# Greippi.net
KiCad netlist of a schematic drawn in EAGLE
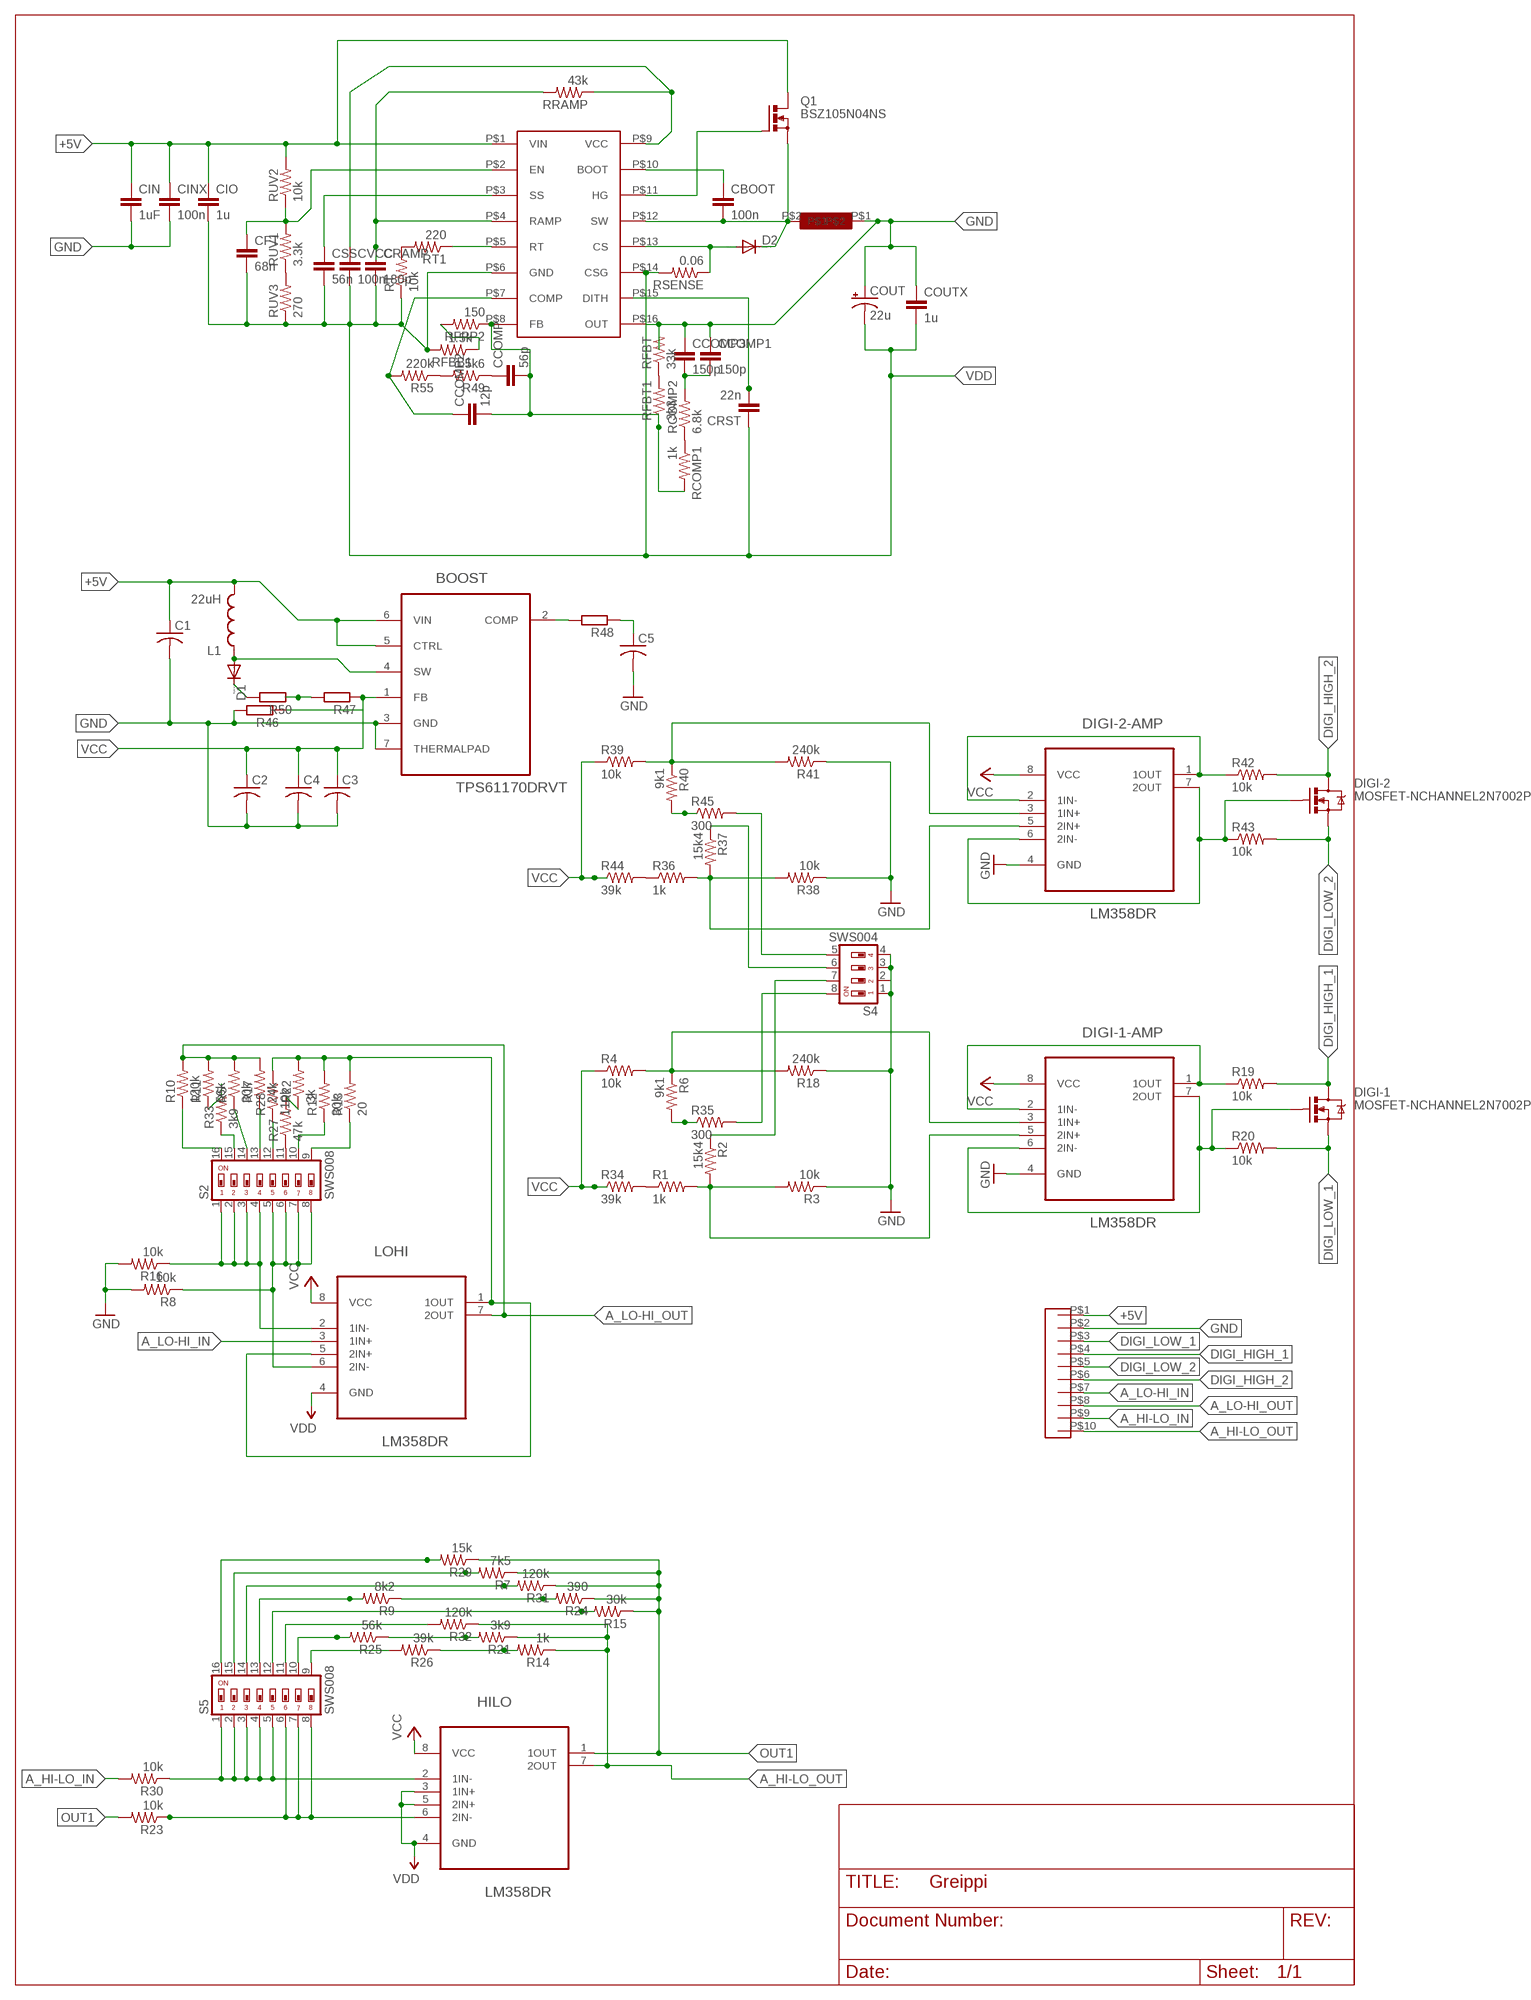
[diagram p0: schematic, sheet 1]

(export (version "E")
  (design (tool "Eeschema 10.0.6"))
  (components
    (comp (ref "BOOST")
      (value "TPS61170DRVT")
      (footprint "eagle-import:SON65P210X210X80-7N")
      (libsource (lib "eagle-import") (part "TPS61170DRVT"))
    )
    (comp (ref "C1")
      (value "C-USC1206")
      (footprint "eagle-import:C1206")
      (libsource (lib "eagle-import") (part "C-USC1206"))
    )
    (comp (ref "C2")
      (value "C-USC0805")
      (footprint "eagle-import:C0805")
      (libsource (lib "eagle-import") (part "C-USC0805"))
    )
    (comp (ref "C3")
      (value "C-USC1206")
      (footprint "eagle-import:C1206")
      (libsource (lib "eagle-import") (part "C-USC1206"))
    )
    (comp (ref "C4")
      (value "C-USC1206")
      (footprint "eagle-import:C1206")
      (libsource (lib "eagle-import") (part "C-USC1206"))
    )
    (comp (ref "C5")
      (value "C-USC1206")
      (footprint "eagle-import:C1206")
      (libsource (lib "eagle-import") (part "C-USC1206"))
    )
    (comp (ref "CBOOT")
      (value "100n")
      (footprint "eagle-import:C0805")
      (libsource (lib "eagle-import") (part "C-EUC0805"))
    )
    (comp (ref "CCOMP")
      (value "56p")
      (footprint "eagle-import:C0805")
      (libsource (lib "eagle-import") (part "C-EUC0805"))
    )
    (comp (ref "CCOMP1")
      (value "150p")
      (footprint "eagle-import:C0805")
      (libsource (lib "eagle-import") (part "C-EUC0805"))
    )
    (comp (ref "CCOMP2")
      (value "12p")
      (footprint "eagle-import:C0805")
      (libsource (lib "eagle-import") (part "C-EUC0805"))
    )
    (comp (ref "CCOMP3")
      (value "150p")
      (footprint "eagle-import:C0805")
      (libsource (lib "eagle-import") (part "C-EUC0805"))
    )
    (comp (ref "CFT")
      (value "68n")
      (footprint "eagle-import:C0805")
      (libsource (lib "eagle-import") (part "C-EUC0805"))
    )
    (comp (ref "CIN")
      (value "1uF")
      (footprint "eagle-import:C0805")
      (libsource (lib "eagle-import") (part "C-EUC0805"))
    )
    (comp (ref "CINX")
      (value "100n")
      (footprint "eagle-import:C0805")
      (libsource (lib "eagle-import") (part "C-EUC0805"))
    )
    (comp (ref "CIO")
      (value "1u")
      (footprint "eagle-import:C0805")
      (libsource (lib "eagle-import") (part "C-EUC0805"))
    )
    (comp (ref "COUT")
      (value "22u")
      (footprint "eagle-import:E5-5")
      (libsource (lib "eagle-import") (part "CPOL-USE5-5"))
    )
    (comp (ref "COUTX")
      (value "1u")
      (footprint "eagle-import:C0805")
      (libsource (lib "eagle-import") (part "C-EUC0805"))
    )
    (comp (ref "CRAMP")
      (value "180p")
      (footprint "eagle-import:C0805")
      (libsource (lib "eagle-import") (part "C-EUC0805"))
    )
    (comp (ref "CRST")
      (value "22n")
      (footprint "eagle-import:C0805")
      (libsource (lib "eagle-import") (part "C-EUC0805"))
    )
    (comp (ref "CSS")
      (value "56n")
      (footprint "eagle-import:C0805")
      (libsource (lib "eagle-import") (part "C-EUC0805"))
    )
    (comp (ref "CVCC")
      (value "100n")
      (footprint "eagle-import:C0805")
      (libsource (lib "eagle-import") (part "C-EUC0805"))
    )
    (comp (ref "D1")
      (value "DIODE-SOD123")
      (footprint "eagle-import:SOD123")
      (libsource (lib "eagle-import") (part "DIODE-SOD123"))
    )
    (comp (ref "D2")
      (value "DIODE-SOD123")
      (footprint "eagle-import:SOD123")
      (libsource (lib "eagle-import") (part "DIODE-SOD123"))
    )
    (comp (ref "DIGI-1")
      (value "MOSFET-NCHANNEL2N7002PW")
      (footprint "eagle-import:SOT323")
      (libsource (lib "eagle-import") (part "MOSFET-NCHANNEL2N7002PW"))
    )
    (comp (ref "DIGI-1-AMP")
      (value "LM358DR")
      (footprint "eagle-import:SOIC127P600X175-8N")
      (libsource (lib "eagle-import") (part "LM358DR"))
    )
    (comp (ref "DIGI-2")
      (value "MOSFET-NCHANNEL2N7002PW")
      (footprint "eagle-import:SOT323")
      (libsource (lib "eagle-import") (part "MOSFET-NCHANNEL2N7002PW"))
    )
    (comp (ref "DIGI-2-AMP")
      (value "LM358DR")
      (footprint "eagle-import:SOIC127P600X175-8N")
      (libsource (lib "eagle-import") (part "LM358DR"))
    )
    (comp (ref "HILO")
      (value "LM358DR")
      (footprint "eagle-import:SOIC127P600X175-8N")
      (libsource (lib "eagle-import") (part "LM358DR"))
    )
    (comp (ref "L1")
      (value "22uH")
      (footprint "eagle-import:SRN6045")
      (libsource (lib "eagle-import") (part "INDUCTORBOURNS_SRN6045"))
    )
    (comp (ref "LOHI")
      (value "LM358DR")
      (footprint "eagle-import:SOIC127P600X175-8N")
      (libsource (lib "eagle-import") (part "LM358DR"))
    )
    (comp (ref "Q1")
      (value "BSZ105N04NS")
      (footprint "eagle-import:PG-TDSON-8")
      (libsource (lib "eagle-import") (part "BSZ105N04NS"))
    )
    (comp (ref "R1")
      (value "1k")
      (footprint "eagle-import:R0805")
      (libsource (lib "eagle-import") (part "R-US_R0805"))
    )
    (comp (ref "R2")
      (value "15k4")
      (footprint "eagle-import:R0805")
      (libsource (lib "eagle-import") (part "R-US_R0805"))
    )
    (comp (ref "R3")
      (value "10k")
      (footprint "eagle-import:R0805")
      (libsource (lib "eagle-import") (part "R-US_R0805"))
    )
    (comp (ref "R4")
      (value "10k")
      (footprint "eagle-import:R0805")
      (libsource (lib "eagle-import") (part "R-US_R0805"))
    )
    (comp (ref "R5")
      (value "30k")
      (footprint "eagle-import:R0805")
      (libsource (lib "eagle-import") (part "R-US_R0805"))
    )
    (comp (ref "R6")
      (value "9k1")
      (footprint "eagle-import:R0805")
      (libsource (lib "eagle-import") (part "R-US_R0805"))
    )
    (comp (ref "R7")
      (value "7k5")
      (footprint "eagle-import:R0805")
      (libsource (lib "eagle-import") (part "R-US_R0805"))
    )
    (comp (ref "R8")
      (value "10k")
      (footprint "eagle-import:R0805")
      (libsource (lib "eagle-import") (part "R-US_R0805"))
    )
    (comp (ref "R9")
      (value "8k2")
      (footprint "eagle-import:R0805")
      (libsource (lib "eagle-import") (part "R-US_R0805"))
    )
    (comp (ref "R10")
      (value "120k")
      (footprint "eagle-import:R0805")
      (libsource (lib "eagle-import") (part "R-US_R0805"))
    )
    (comp (ref "R11")
      (value "56k")
      (footprint "eagle-import:R0805")
      (libsource (lib "eagle-import") (part "R-US_R0805"))
    )
    (comp (ref "R12")
      (value "30k")
      (footprint "eagle-import:R0805")
      (libsource (lib "eagle-import") (part "R-US_R0805"))
    )
    (comp (ref "R13")
      (value "20")
      (footprint "eagle-import:R0805")
      (libsource (lib "eagle-import") (part "R-US_R0805"))
    )
    (comp (ref "R14")
      (value "1k")
      (footprint "eagle-import:R0805")
      (libsource (lib "eagle-import") (part "R-US_R0805"))
    )
    (comp (ref "R15")
      (value "30k")
      (footprint "eagle-import:R0805")
      (libsource (lib "eagle-import") (part "R-US_R0805"))
    )
    (comp (ref "R16")
      (value "10k")
      (footprint "eagle-import:R0805")
      (libsource (lib "eagle-import") (part "R-US_R0805"))
    )
    (comp (ref "R17")
      (value "24k")
      (footprint "eagle-import:R0805")
      (libsource (lib "eagle-import") (part "R-US_R0805"))
    )
    (comp (ref "R18")
      (value "240k")
      (footprint "eagle-import:R0805")
      (libsource (lib "eagle-import") (part "R-US_R0805"))
    )
    (comp (ref "R19")
      (value "10k")
      (footprint "eagle-import:R0805")
      (libsource (lib "eagle-import") (part "R-US_R0805"))
    )
    (comp (ref "R20")
      (value "10k")
      (footprint "eagle-import:R0805")
      (libsource (lib "eagle-import") (part "R-US_R0805"))
    )
    (comp (ref "R21")
      (value "3k9")
      (footprint "eagle-import:R0805")
      (libsource (lib "eagle-import") (part "R-US_R0805"))
    )
    (comp (ref "R22")
      (value "3k")
      (footprint "eagle-import:R0805")
      (libsource (lib "eagle-import") (part "R-US_R0805"))
    )
    (comp (ref "R23")
      (value "10k")
      (footprint "eagle-import:R0805")
      (libsource (lib "eagle-import") (part "R-US_R0805"))
    )
    (comp (ref "R24")
      (value "390")
      (footprint "eagle-import:R0805")
      (libsource (lib "eagle-import") (part "R-US_R0805"))
    )
    (comp (ref "R25")
      (value "56k")
      (footprint "eagle-import:R0805")
      (libsource (lib "eagle-import") (part "R-US_R0805"))
    )
    (comp (ref "R26")
      (value "39k")
      (footprint "eagle-import:R0805")
      (libsource (lib "eagle-import") (part "R-US_R0805"))
    )
    (comp (ref "R27")
      (value "47k")
      (footprint "eagle-import:R0805")
      (libsource (lib "eagle-import") (part "R-US_R0805"))
    )
    (comp (ref "R28")
      (value "110k")
      (footprint "eagle-import:R0805")
      (libsource (lib "eagle-import") (part "R-US_R0805"))
    )
    (comp (ref "R29")
      (value "15k")
      (footprint "eagle-import:R0805")
      (libsource (lib "eagle-import") (part "R-US_R0805"))
    )
    (comp (ref "R30")
      (value "10k")
      (footprint "eagle-import:R0805")
      (libsource (lib "eagle-import") (part "R-US_R0805"))
    )
    (comp (ref "R31")
      (value "120k")
      (footprint "eagle-import:R0805")
      (libsource (lib "eagle-import") (part "R-US_R0805"))
    )
    (comp (ref "R32")
      (value "120k")
      (footprint "eagle-import:R0805")
      (libsource (lib "eagle-import") (part "R-US_R0805"))
    )
    (comp (ref "R33")
      (value "3k9")
      (footprint "eagle-import:R0805")
      (libsource (lib "eagle-import") (part "R-US_R0805"))
    )
    (comp (ref "R34")
      (value "39k")
      (footprint "eagle-import:R0805")
      (libsource (lib "eagle-import") (part "R-US_R0805"))
    )
    (comp (ref "R35")
      (value "300")
      (footprint "eagle-import:R0805")
      (libsource (lib "eagle-import") (part "R-US_R0805"))
    )
    (comp (ref "R36")
      (value "1k")
      (footprint "eagle-import:R0805")
      (libsource (lib "eagle-import") (part "R-US_R0805"))
    )
    (comp (ref "R37")
      (value "15k4")
      (footprint "eagle-import:R0805")
      (libsource (lib "eagle-import") (part "R-US_R0805"))
    )
    (comp (ref "R38")
      (value "10k")
      (footprint "eagle-import:R0805")
      (libsource (lib "eagle-import") (part "R-US_R0805"))
    )
    (comp (ref "R39")
      (value "10k")
      (footprint "eagle-import:R0805")
      (libsource (lib "eagle-import") (part "R-US_R0805"))
    )
    (comp (ref "R40")
      (value "9k1")
      (footprint "eagle-import:R0805")
      (libsource (lib "eagle-import") (part "R-US_R0805"))
    )
    (comp (ref "R41")
      (value "240k")
      (footprint "eagle-import:R0805")
      (libsource (lib "eagle-import") (part "R-US_R0805"))
    )
    (comp (ref "R42")
      (value "10k")
      (footprint "eagle-import:R0805")
      (libsource (lib "eagle-import") (part "R-US_R0805"))
    )
    (comp (ref "R43")
      (value "10k")
      (footprint "eagle-import:R0805")
      (libsource (lib "eagle-import") (part "R-US_R0805"))
    )
    (comp (ref "R44")
      (value "39k")
      (footprint "eagle-import:R0805")
      (libsource (lib "eagle-import") (part "R-US_R0805"))
    )
    (comp (ref "R45")
      (value "300")
      (footprint "eagle-import:R0805")
      (libsource (lib "eagle-import") (part "R-US_R0805"))
    )
    (comp (ref "R46")
      (value "R-EU_R0805")
      (footprint "eagle-import:R0805")
      (libsource (lib "eagle-import") (part "R-EU_R0805"))
    )
    (comp (ref "R47")
      (value "R-EU_R0805")
      (footprint "eagle-import:R0805")
      (libsource (lib "eagle-import") (part "R-EU_R0805"))
    )
    (comp (ref "R48")
      (value "R-EU_R0805")
      (footprint "eagle-import:R0805")
      (libsource (lib "eagle-import") (part "R-EU_R0805"))
    )
    (comp (ref "R49")
      (value "5k6")
      (footprint "eagle-import:R0805")
      (libsource (lib "eagle-import") (part "R-US_R0805"))
    )
    (comp (ref "R50")
      (value "R-EU_R0805")
      (footprint "eagle-import:R0805")
      (libsource (lib "eagle-import") (part "R-EU_R0805"))
    )
    (comp (ref "R55")
      (value "220k")
      (footprint "eagle-import:R0805")
      (libsource (lib "eagle-import") (part "R-US_R0805"))
    )
    (comp (ref "RCOMP1")
      (value "1k")
      (footprint "eagle-import:R0805")
      (libsource (lib "eagle-import") (part "R-US_R0805"))
    )
    (comp (ref "RCOMP2")
      (value "6.8k")
      (footprint "eagle-import:R0805")
      (libsource (lib "eagle-import") (part "R-US_R0805"))
    )
    (comp (ref "RFBB1")
      (value "1.5k")
      (footprint "eagle-import:R0805")
      (libsource (lib "eagle-import") (part "R-US_R0805"))
    )
    (comp (ref "RFBT")
      (value "33k")
      (footprint "eagle-import:R0805")
      (libsource (lib "eagle-import") (part "R-US_R0805"))
    )
    (comp (ref "RFBT1")
      (value "3k3")
      (footprint "eagle-import:R0805")
      (libsource (lib "eagle-import") (part "R-US_R0805"))
    )
    (comp (ref "RFPP2")
      (value "150")
      (footprint "eagle-import:R0805")
      (libsource (lib "eagle-import") (part "R-US_R0805"))
    )
    (comp (ref "RRAMP")
      (value "43k")
      (footprint "eagle-import:R0805")
      (libsource (lib "eagle-import") (part "R-US_R0805"))
    )
    (comp (ref "RSENSE")
      (value "0.06")
      (footprint "eagle-import:R0805")
      (libsource (lib "eagle-import") (part "R-US_R0805"))
    )
    (comp (ref "RT")
      (value "10k")
      (footprint "eagle-import:R0805")
      (libsource (lib "eagle-import") (part "R-US_R0805"))
    )
    (comp (ref "RT1")
      (value "220")
      (footprint "eagle-import:R0805")
      (libsource (lib "eagle-import") (part "R-US_R0805"))
    )
    (comp (ref "RUV1")
      (value "3.3k")
      (footprint "eagle-import:R0805")
      (libsource (lib "eagle-import") (part "R-US_R0805"))
    )
    (comp (ref "RUV2")
      (value "10k")
      (footprint "eagle-import:R0805")
      (libsource (lib "eagle-import") (part "R-US_R0805"))
    )
    (comp (ref "RUV3")
      (value "270")
      (footprint "eagle-import:R0805")
      (libsource (lib "eagle-import") (part "R-US_R0805"))
    )
    (comp (ref "S2")
      (value "SWS008")
      (footprint "eagle-import:SMS-008")
      (libsource (lib "eagle-import") (part "SWS008"))
    )
    (comp (ref "S4")
      (value "SWS004")
      (footprint "eagle-import:SMS-004")
      (libsource (lib "eagle-import") (part "SWS004"))
    )
    (comp (ref "S5")
      (value "SWS008")
      (footprint "eagle-import:SMS-008")
      (libsource (lib "eagle-import") (part "SWS008"))
    )
    (comp (ref "U$1")
      (value "5.08PITCHTERMINAL")
      (footprint "eagle-import:10KPL508")
      (libsource (lib "eagle-import") (part "5.08PITCHTERMINAL"))
    )
    (comp (ref "U$2")
      (value "LM5088")
      (footprint "eagle-import:LM5088")
      (libsource (lib "eagle-import") (part "LM5088"))
    )
    (comp (ref "U$3")
      (value "KLICK_INDUCTOR01")
      (footprint "eagle-import:KLICK_INDUCTOR01")
      (libsource (lib "eagle-import") (part "KLICK_INDUCTOR01"))
    )
  )
  (nets
    (net (code "1") (name "+5V") (class "Default")
      (node (ref "BOOST") (pin "5") (pinfunction "CTRL_5") (pintype "input"))
      (node (ref "BOOST") (pin "6") (pinfunction "VIN_6") (pintype "power_in"))
      (node (ref "C1") (pin "1") (pinfunction "1_1") (pintype "passive"))
      (node (ref "CIN") (pin "1") (pinfunction "1_1") (pintype "passive"))
      (node (ref "CINX") (pin "1") (pinfunction "1_1") (pintype "passive"))
      (node (ref "CIO") (pin "1") (pinfunction "1_1") (pintype "passive"))
      (node (ref "L1") (pin "2") (pinfunction "2_2") (pintype "passive"))
      (node (ref "Q1") (pin "5") (pinfunction "D_5") (pintype "passive"))
      (node (ref "Q1") (pin "6") (pinfunction "D_6") (pintype "passive"))
      (node (ref "Q1") (pin "7") (pinfunction "D_7") (pintype "passive"))
      (node (ref "Q1") (pin "8") (pinfunction "D_8") (pintype "passive"))
      (node (ref "Q1") (pin "TH") (pinfunction "D_TH") (pintype "passive"))
      (node (ref "RUV2") (pin "2") (pinfunction "2_2") (pintype "passive"))
      (node (ref "U$1") (pin "P$1") (pinfunction "P$1_P$1") (pintype "bidirectional"))
      (node (ref "U$2") (pin "P$1") (pinfunction "VIN_P$1") (pintype "bidirectional"))
    )
    (net (code "2") (name "A_HI-LO_IN") (class "Default")
      (node (ref "R30") (pin "2") (pinfunction "2_2") (pintype "passive"))
      (node (ref "U$1") (pin "P$9") (pinfunction "P$9_P$9") (pintype "bidirectional"))
    )
    (net (code "3") (name "A_HI-LO_OUT") (class "Default")
      (node (ref "HILO") (pin "7") (pinfunction "2OUT_7") (pintype "output"))
      (node (ref "R14") (pin "1") (pinfunction "1_1") (pintype "passive"))
      (node (ref "R21") (pin "1") (pinfunction "1_1") (pintype "passive"))
      (node (ref "R32") (pin "1") (pinfunction "1_1") (pintype "passive"))
      (node (ref "U$1") (pin "P$10") (pinfunction "P$10_P$10") (pintype "bidirectional"))
    )
    (net (code "4") (name "A_LO-HI_IN") (class "Default")
      (node (ref "LOHI") (pin "3") (pinfunction "1IN+_3") (pintype "input"))
      (node (ref "U$1") (pin "P$7") (pinfunction "P$7_P$7") (pintype "bidirectional"))
    )
    (net (code "5") (name "A_LO-HI_OUT") (class "Default")
      (node (ref "LOHI") (pin "7") (pinfunction "2OUT_7") (pintype "output"))
      (node (ref "R10") (pin "2") (pinfunction "2_2") (pintype "passive"))
      (node (ref "R11") (pin "2") (pinfunction "2_2") (pintype "passive"))
      (node (ref "R17") (pin "2") (pinfunction "2_2") (pintype "passive"))
      (node (ref "R5") (pin "2") (pinfunction "2_2") (pintype "passive"))
      (node (ref "U$1") (pin "P$8") (pinfunction "P$8_P$8") (pintype "bidirectional"))
    )
    (net (code "6") (name "DIGI_HIGH_1") (class "Default")
      (node (ref "DIGI-1") (pin "3") (pinfunction "D_3") (pintype "passive"))
      (node (ref "R19") (pin "2") (pinfunction "2_2") (pintype "passive"))
      (node (ref "U$1") (pin "P$4") (pinfunction "P$4_P$4") (pintype "bidirectional"))
    )
    (net (code "7") (name "DIGI_HIGH_2") (class "Default")
      (node (ref "DIGI-2") (pin "3") (pinfunction "D_3") (pintype "passive"))
      (node (ref "R42") (pin "2") (pinfunction "2_2") (pintype "passive"))
      (node (ref "U$1") (pin "P$6") (pinfunction "P$6_P$6") (pintype "bidirectional"))
    )
    (net (code "8") (name "DIGI_LOW_1") (class "Default")
      (node (ref "DIGI-1") (pin "2") (pinfunction "S_2") (pintype "passive"))
      (node (ref "R20") (pin "2") (pinfunction "2_2") (pintype "passive"))
      (node (ref "U$1") (pin "P$3") (pinfunction "P$3_P$3") (pintype "bidirectional"))
    )
    (net (code "9") (name "DIGI_LOW_2") (class "Default")
      (node (ref "DIGI-2") (pin "2") (pinfunction "S_2") (pintype "passive"))
      (node (ref "R43") (pin "2") (pinfunction "2_2") (pintype "passive"))
      (node (ref "U$1") (pin "P$5") (pinfunction "P$5_P$5") (pintype "bidirectional"))
    )
    (net (code "10") (name "GND") (class "Default")
      (node (ref "BOOST") (pin "3") (pinfunction "GND_3") (pintype "passive"))
      (node (ref "BOOST") (pin "7") (pinfunction "THERMALPAD_7") (pintype "passive"))
      (node (ref "C1") (pin "2") (pinfunction "2_2") (pintype "passive"))
      (node (ref "C2") (pin "2") (pinfunction "2_2") (pintype "passive"))
      (node (ref "C3") (pin "2") (pinfunction "2_2") (pintype "passive"))
      (node (ref "C4") (pin "2") (pinfunction "2_2") (pintype "passive"))
      (node (ref "C5") (pin "2") (pinfunction "2_2") (pintype "passive"))
      (node (ref "CCOMP1") (pin "1") (pinfunction "1_1") (pintype "passive"))
      (node (ref "CCOMP3") (pin "1") (pinfunction "1_1") (pintype "passive"))
      (node (ref "CIN") (pin "2") (pinfunction "2_2") (pintype "passive"))
      (node (ref "CINX") (pin "2") (pinfunction "2_2") (pintype "passive"))
      (node (ref "COUT") (pin "+") (pinfunction "+_+") (pintype "passive"))
      (node (ref "COUTX") (pin "1") (pinfunction "1_1") (pintype "passive"))
      (node (ref "DIGI-1-AMP") (pin "4") (pinfunction "GND_4") (pintype "passive"))
      (node (ref "DIGI-2-AMP") (pin "4") (pinfunction "GND_4") (pintype "passive"))
      (node (ref "R16") (pin "2") (pinfunction "2_2") (pintype "passive"))
      (node (ref "R18") (pin "1") (pinfunction "1_1") (pintype "passive"))
      (node (ref "R3") (pin "1") (pinfunction "1_1") (pintype "passive"))
      (node (ref "R38") (pin "1") (pinfunction "1_1") (pintype "passive"))
      (node (ref "R41") (pin "1") (pinfunction "1_1") (pintype "passive"))
      (node (ref "R46") (pin "2") (pinfunction "2_2") (pintype "passive"))
      (node (ref "R8") (pin "2") (pinfunction "2_2") (pintype "passive"))
      (node (ref "RFBT") (pin "2") (pinfunction "2_2") (pintype "passive"))
      (node (ref "S4") (pin "1") (pinfunction "1_1") (pintype "passive"))
      (node (ref "S4") (pin "2") (pinfunction "2_2") (pintype "passive"))
      (node (ref "S4") (pin "3") (pinfunction "3_3") (pintype "passive"))
      (node (ref "S4") (pin "4") (pinfunction "4_4") (pintype "passive"))
      (node (ref "U$1") (pin "P$2") (pinfunction "P$2_P$2") (pintype "bidirectional"))
      (node (ref "U$2") (pin "P$16") (pinfunction "OUT_P$16") (pintype "bidirectional"))
      (node (ref "U$3") (pin "P$1") (pinfunction "P$1_P$1") (pintype "bidirectional"))
    )
    (net (code "11") (name "Net-(BOOST-COMP)") (class "Default")
      (node (ref "BOOST") (pin "2") (pinfunction "COMP_2") (pintype "output"))
      (node (ref "R48") (pin "2") (pinfunction "2_2") (pintype "passive"))
    )
    (net (code "12") (name "Net-(BOOST-SW)") (class "Default")
      (node (ref "BOOST") (pin "4") (pinfunction "SW_4") (pintype "input"))
      (node (ref "D1") (pin "A") (pinfunction "A_A") (pintype "passive"))
      (node (ref "L1") (pin "1") (pinfunction "1_1") (pintype "passive"))
    )
    (net (code "13") (name "Net-(C5-Pad1)") (class "Default")
      (node (ref "C5") (pin "1") (pinfunction "1_1") (pintype "passive"))
      (node (ref "R48") (pin "1") (pinfunction "1_1") (pintype "passive"))
    )
    (net (code "14") (name "Net-(CCOMP-Pad1)") (class "Default")
      (node (ref "CCOMP") (pin "1") (pinfunction "1_1") (pintype "passive"))
      (node (ref "R49") (pin "1") (pinfunction "1_1") (pintype "passive"))
    )
    (net (code "15") (name "Net-(CCOMP1-Pad2)") (class "Default")
      (node (ref "CCOMP1") (pin "2") (pinfunction "2_2") (pintype "passive"))
      (node (ref "CCOMP3") (pin "2") (pinfunction "2_2") (pintype "passive"))
      (node (ref "RCOMP2") (pin "2") (pinfunction "2_2") (pintype "passive"))
    )
    (net (code "16") (name "Net-(D1-PadC)") (class "Default")
      (node (ref "D1") (pin "C") (pinfunction "C_C") (pintype "passive"))
      (node (ref "R50") (pin "2") (pinfunction "2_2") (pintype "passive"))
    )
    (net (code "17") (name "Net-(DIGI-1-AMP-1IN+)") (class "Default")
      (node (ref "DIGI-1-AMP") (pin "3") (pinfunction "1IN+_3") (pintype "input"))
      (node (ref "R18") (pin "2") (pinfunction "2_2") (pintype "passive"))
      (node (ref "R4") (pin "2") (pinfunction "2_2") (pintype "passive"))
      (node (ref "R6") (pin "1") (pinfunction "1_1") (pintype "passive"))
    )
    (net (code "18") (name "Net-(DIGI-1-AMP-1IN-)") (class "Default")
      (node (ref "DIGI-1-AMP") (pin "1") (pinfunction "1OUT_1") (pintype "output"))
      (node (ref "DIGI-1-AMP") (pin "2") (pinfunction "1IN-_2") (pintype "input"))
      (node (ref "R19") (pin "1") (pinfunction "1_1") (pintype "passive"))
    )
    (net (code "19") (name "Net-(DIGI-1-AMP-2IN+)") (class "Default")
      (node (ref "DIGI-1-AMP") (pin "5") (pinfunction "2IN+_5") (pintype "input"))
      (node (ref "R1") (pin "2") (pinfunction "2_2") (pintype "passive"))
      (node (ref "R2") (pin "2") (pinfunction "2_2") (pintype "passive"))
      (node (ref "R3") (pin "2") (pinfunction "2_2") (pintype "passive"))
    )
    (net (code "20") (name "Net-(DIGI-1-AMP-2IN-)") (class "Default")
      (node (ref "DIGI-1") (pin "1") (pinfunction "G_1") (pintype "passive"))
      (node (ref "DIGI-1-AMP") (pin "6") (pinfunction "2IN-_6") (pintype "input"))
      (node (ref "DIGI-1-AMP") (pin "7") (pinfunction "2OUT_7") (pintype "output"))
      (node (ref "R20") (pin "1") (pinfunction "1_1") (pintype "passive"))
    )
    (net (code "21") (name "Net-(DIGI-2-AMP-1IN+)") (class "Default")
      (node (ref "DIGI-2-AMP") (pin "3") (pinfunction "1IN+_3") (pintype "input"))
      (node (ref "R39") (pin "2") (pinfunction "2_2") (pintype "passive"))
      (node (ref "R40") (pin "1") (pinfunction "1_1") (pintype "passive"))
      (node (ref "R41") (pin "2") (pinfunction "2_2") (pintype "passive"))
    )
    (net (code "22") (name "Net-(DIGI-2-AMP-1IN-)") (class "Default")
      (node (ref "DIGI-2-AMP") (pin "1") (pinfunction "1OUT_1") (pintype "output"))
      (node (ref "DIGI-2-AMP") (pin "2") (pinfunction "1IN-_2") (pintype "input"))
      (node (ref "R42") (pin "1") (pinfunction "1_1") (pintype "passive"))
    )
    (net (code "23") (name "Net-(DIGI-2-AMP-2IN+)") (class "Default")
      (node (ref "DIGI-2-AMP") (pin "5") (pinfunction "2IN+_5") (pintype "input"))
      (node (ref "R36") (pin "2") (pinfunction "2_2") (pintype "passive"))
      (node (ref "R37") (pin "2") (pinfunction "2_2") (pintype "passive"))
      (node (ref "R38") (pin "2") (pinfunction "2_2") (pintype "passive"))
    )
    (net (code "24") (name "Net-(DIGI-2-AMP-2IN-)") (class "Default")
      (node (ref "DIGI-2") (pin "1") (pinfunction "G_1") (pintype "passive"))
      (node (ref "DIGI-2-AMP") (pin "6") (pinfunction "2IN-_6") (pintype "input"))
      (node (ref "DIGI-2-AMP") (pin "7") (pinfunction "2OUT_7") (pintype "output"))
      (node (ref "R43") (pin "1") (pinfunction "1_1") (pintype "passive"))
    )
    (net (code "25") (name "Net-(HILO-1IN-)") (class "Default")
      (node (ref "HILO") (pin "2") (pinfunction "1IN-_2") (pintype "input"))
      (node (ref "R30") (pin "1") (pinfunction "1_1") (pintype "passive"))
      (node (ref "S5") (pin "1") (pinfunction "1_1") (pintype "passive"))
      (node (ref "S5") (pin "2") (pinfunction "2_2") (pintype "passive"))
      (node (ref "S5") (pin "3") (pinfunction "3_3") (pintype "passive"))
      (node (ref "S5") (pin "4") (pinfunction "4_4") (pintype "passive"))
      (node (ref "S5") (pin "5") (pinfunction "5_5") (pintype "passive"))
    )
    (net (code "26") (name "Net-(HILO-2IN-)") (class "Default")
      (node (ref "HILO") (pin "6") (pinfunction "2IN-_6") (pintype "input"))
      (node (ref "R23") (pin "1") (pinfunction "1_1") (pintype "passive"))
      (node (ref "S5") (pin "6") (pinfunction "6_6") (pintype "passive"))
      (node (ref "S5") (pin "7") (pinfunction "7_7") (pintype "passive"))
      (node (ref "S5") (pin "8") (pinfunction "8_8") (pintype "passive"))
    )
    (net (code "27") (name "Net-(LOHI-1IN-)") (class "Default")
      (node (ref "LOHI") (pin "2") (pinfunction "1IN-_2") (pintype "input"))
      (node (ref "R16") (pin "1") (pinfunction "1_1") (pintype "passive"))
      (node (ref "S2") (pin "1") (pinfunction "1_1") (pintype "passive"))
      (node (ref "S2") (pin "2") (pinfunction "2_2") (pintype "passive"))
      (node (ref "S2") (pin "3") (pinfunction "3_3") (pintype "passive"))
      (node (ref "S2") (pin "4") (pinfunction "4_4") (pintype "passive"))
    )
    (net (code "28") (name "Net-(LOHI-1OUT)") (class "Default")
      (node (ref "LOHI") (pin "1") (pinfunction "1OUT_1") (pintype "output"))
      (node (ref "LOHI") (pin "5") (pinfunction "2IN+_5") (pintype "input"))
      (node (ref "R12") (pin "2") (pinfunction "2_2") (pintype "passive"))
      (node (ref "R13") (pin "2") (pinfunction "2_2") (pintype "passive"))
      (node (ref "R22") (pin "2") (pinfunction "2_2") (pintype "passive"))
      (node (ref "R28") (pin "2") (pinfunction "2_2") (pintype "passive"))
    )
    (net (code "29") (name "Net-(LOHI-2IN-)") (class "Default")
      (node (ref "LOHI") (pin "6") (pinfunction "2IN-_6") (pintype "input"))
      (node (ref "R8") (pin "1") (pinfunction "1_1") (pintype "passive"))
      (node (ref "S2") (pin "5") (pinfunction "5_5") (pintype "passive"))
      (node (ref "S2") (pin "6") (pinfunction "6_6") (pintype "passive"))
      (node (ref "S2") (pin "7") (pinfunction "7_7") (pintype "passive"))
      (node (ref "S2") (pin "8") (pinfunction "8_8") (pintype "passive"))
    )
    (net (code "30") (name "Net-(Q1-G)") (class "Default")
      (node (ref "Q1") (pin "4") (pinfunction "G_4") (pintype "passive"))
      (node (ref "U$2") (pin "P$11") (pinfunction "HG_P$11") (pintype "bidirectional"))
    )
    (net (code "31") (name "Net-(R1-Pad1)") (class "Default")
      (node (ref "R1") (pin "1") (pinfunction "1_1") (pintype "passive"))
      (node (ref "R34") (pin "2") (pinfunction "2_2") (pintype "passive"))
    )
    (net (code "32") (name "Net-(R2-Pad1)") (class "Default")
      (node (ref "R2") (pin "1") (pinfunction "1_1") (pintype "passive"))
      (node (ref "S4") (pin "7") (pinfunction "7_7") (pintype "passive"))
    )
    (net (code "33") (name "Net-(R5-Pad1)") (class "Default")
      (node (ref "R5") (pin "1") (pinfunction "1_1") (pintype "passive"))
      (node (ref "S2") (pin "14") (pinfunction "14_14") (pintype "passive"))
    )
    (net (code "34") (name "Net-(R7-Pad2)") (class "Default")
      (node (ref "R7") (pin "2") (pinfunction "2_2") (pintype "passive"))
      (node (ref "S5") (pin "15") (pinfunction "15_15") (pintype "passive"))
    )
    (net (code "35") (name "Net-(R9-Pad2)") (class "Default")
      (node (ref "R9") (pin "2") (pinfunction "2_2") (pintype "passive"))
      (node (ref "S5") (pin "13") (pinfunction "13_13") (pintype "passive"))
    )
    (net (code "36") (name "Net-(R10-Pad1)") (class "Default")
      (node (ref "R10") (pin "1") (pinfunction "1_1") (pintype "passive"))
      (node (ref "S2") (pin "16") (pinfunction "16_16") (pintype "passive"))
    )
    (net (code "37") (name "Net-(R11-Pad1)") (class "Default")
      (node (ref "R11") (pin "1") (pinfunction "1_1") (pintype "passive"))
      (node (ref "R33") (pin "2") (pinfunction "2_2") (pintype "passive"))
    )
    (net (code "38") (name "Net-(R12-Pad1)") (class "Default")
      (node (ref "R12") (pin "1") (pinfunction "1_1") (pintype "passive"))
      (node (ref "S2") (pin "10") (pinfunction "10_10") (pintype "passive"))
    )
    (net (code "39") (name "Net-(R13-Pad1)") (class "Default")
      (node (ref "R13") (pin "1") (pinfunction "1_1") (pintype "passive"))
      (node (ref "S2") (pin "9") (pinfunction "9_9") (pintype "passive"))
    )
    (net (code "40") (name "Net-(R14-Pad2)") (class "Default")
      (node (ref "R14") (pin "2") (pinfunction "2_2") (pintype "passive"))
      (node (ref "R26") (pin "1") (pinfunction "1_1") (pintype "passive"))
    )
    (net (code "41") (name "Net-(R15-Pad2)") (class "Default")
      (node (ref "R15") (pin "2") (pinfunction "2_2") (pintype "passive"))
      (node (ref "S5") (pin "12") (pinfunction "12_12") (pintype "passive"))
    )
    (net (code "42") (name "Net-(R17-Pad1)") (class "Default")
      (node (ref "R17") (pin "1") (pinfunction "1_1") (pintype "passive"))
      (node (ref "S2") (pin "13") (pinfunction "13_13") (pintype "passive"))
    )
    (net (code "43") (name "Net-(R21-Pad2)") (class "Default")
      (node (ref "R21") (pin "2") (pinfunction "2_2") (pintype "passive"))
      (node (ref "R25") (pin "1") (pinfunction "1_1") (pintype "passive"))
    )
    (net (code "44") (name "Net-(R22-Pad1)") (class "Default")
      (node (ref "R22") (pin "1") (pinfunction "1_1") (pintype "passive"))
      (node (ref "R27") (pin "2") (pinfunction "2_2") (pintype "passive"))
    )
    (net (code "45") (name "Net-(R24-Pad2)") (class "Default")
      (node (ref "R24") (pin "2") (pinfunction "2_2") (pintype "passive"))
      (node (ref "R9") (pin "1") (pinfunction "1_1") (pintype "passive"))
    )
    (net (code "46") (name "Net-(R25-Pad2)") (class "Default")
      (node (ref "R25") (pin "2") (pinfunction "2_2") (pintype "passive"))
      (node (ref "S5") (pin "10") (pinfunction "10_10") (pintype "passive"))
    )
    (net (code "47") (name "Net-(R26-Pad2)") (class "Default")
      (node (ref "R26") (pin "2") (pinfunction "2_2") (pintype "passive"))
      (node (ref "S5") (pin "9") (pinfunction "9_9") (pintype "passive"))
    )
    (net (code "48") (name "Net-(R27-Pad1)") (class "Default")
      (node (ref "R27") (pin "1") (pinfunction "1_1") (pintype "passive"))
      (node (ref "S2") (pin "11") (pinfunction "11_11") (pintype "passive"))
    )
    (net (code "49") (name "Net-(R28-Pad1)") (class "Default")
      (node (ref "R28") (pin "1") (pinfunction "1_1") (pintype "passive"))
      (node (ref "S2") (pin "12") (pinfunction "12_12") (pintype "passive"))
    )
    (net (code "50") (name "Net-(R29-Pad2)") (class "Default")
      (node (ref "R29") (pin "2") (pinfunction "2_2") (pintype "passive"))
      (node (ref "S5") (pin "16") (pinfunction "16_16") (pintype "passive"))
    )
    (net (code "51") (name "Net-(R31-Pad2)") (class "Default")
      (node (ref "R31") (pin "2") (pinfunction "2_2") (pintype "passive"))
      (node (ref "S5") (pin "14") (pinfunction "14_14") (pintype "passive"))
    )
    (net (code "52") (name "Net-(R32-Pad2)") (class "Default")
      (node (ref "R32") (pin "2") (pinfunction "2_2") (pintype "passive"))
      (node (ref "S5") (pin "11") (pinfunction "11_11") (pintype "passive"))
    )
    (net (code "53") (name "Net-(R33-Pad1)") (class "Default")
      (node (ref "R33") (pin "1") (pinfunction "1_1") (pintype "passive"))
      (node (ref "S2") (pin "15") (pinfunction "15_15") (pintype "passive"))
    )
    (net (code "54") (name "Net-(R35-Pad1)") (class "Default")
      (node (ref "R35") (pin "1") (pinfunction "1_1") (pintype "passive"))
      (node (ref "R6") (pin "2") (pinfunction "2_2") (pintype "passive"))
    )
    (net (code "55") (name "Net-(R35-Pad2)") (class "Default")
      (node (ref "R35") (pin "2") (pinfunction "2_2") (pintype "passive"))
      (node (ref "S4") (pin "8") (pinfunction "8_8") (pintype "passive"))
    )
    (net (code "56") (name "Net-(R36-Pad1)") (class "Default")
      (node (ref "R36") (pin "1") (pinfunction "1_1") (pintype "passive"))
      (node (ref "R44") (pin "2") (pinfunction "2_2") (pintype "passive"))
    )
    (net (code "57") (name "Net-(R37-Pad1)") (class "Default")
      (node (ref "R37") (pin "1") (pinfunction "1_1") (pintype "passive"))
      (node (ref "S4") (pin "6") (pinfunction "6_6") (pintype "passive"))
    )
    (net (code "58") (name "Net-(R40-Pad2)") (class "Default")
      (node (ref "R40") (pin "2") (pinfunction "2_2") (pintype "passive"))
      (node (ref "R45") (pin "1") (pinfunction "1_1") (pintype "passive"))
    )
    (net (code "59") (name "Net-(R45-Pad2)") (class "Default")
      (node (ref "R45") (pin "2") (pinfunction "2_2") (pintype "passive"))
      (node (ref "S4") (pin "5") (pinfunction "5_5") (pintype "passive"))
    )
    (net (code "60") (name "Net-(R47-Pad2)") (class "Default")
      (node (ref "R47") (pin "2") (pinfunction "2_2") (pintype "passive"))
      (node (ref "R50") (pin "1") (pinfunction "1_1") (pintype "passive"))
    )
    (net (code "61") (name "Net-(R49-Pad2)") (class "Default")
      (node (ref "R49") (pin "2") (pinfunction "2_2") (pintype "passive"))
      (node (ref "R55") (pin "1") (pinfunction "1_1") (pintype "passive"))
    )
    (net (code "62") (name "Net-(RCOMP1-Pad1)") (class "Default")
      (node (ref "RCOMP1") (pin "1") (pinfunction "1_1") (pintype "passive"))
      (node (ref "RCOMP2") (pin "1") (pinfunction "1_1") (pintype "passive"))
    )
    (net (code "63") (name "Net-(RFBB1-Pad1)") (class "Default")
      (node (ref "RFBB1") (pin "1") (pinfunction "1_1") (pintype "passive"))
      (node (ref "RFPP2") (pin "2") (pinfunction "2_2") (pintype "passive"))
    )
    (net (code "64") (name "Net-(RFBT-Pad1)") (class "Default")
      (node (ref "RFBT") (pin "1") (pinfunction "1_1") (pintype "passive"))
      (node (ref "RFBT1") (pin "2") (pinfunction "2_2") (pintype "passive"))
    )
    (net (code "65") (name "Net-(RT-Pad2)") (class "Default")
      (node (ref "RT") (pin "2") (pinfunction "2_2") (pintype "passive"))
      (node (ref "RT1") (pin "2") (pinfunction "2_2") (pintype "passive"))
    )
    (net (code "66") (name "Net-(RUV1-Pad1)") (class "Default")
      (node (ref "RUV1") (pin "1") (pinfunction "1_1") (pintype "passive"))
      (node (ref "RUV3") (pin "2") (pinfunction "2_2") (pintype "passive"))
    )
    (net (code "67") (name "Net-(U$2-BOOT)") (class "Default")
      (node (ref "CBOOT") (pin "1") (pinfunction "1_1") (pintype "passive"))
      (node (ref "U$2") (pin "P$10") (pinfunction "BOOT_P$10") (pintype "bidirectional"))
    )
    (net (code "68") (name "Net-(U$2-COMP)") (class "Default")
      (node (ref "CCOMP2") (pin "1") (pinfunction "1_1") (pintype "passive"))
      (node (ref "R55") (pin "2") (pinfunction "2_2") (pintype "passive"))
      (node (ref "U$2") (pin "P$7") (pinfunction "COMP_P$7") (pintype "bidirectional"))
    )
    (net (code "69") (name "Net-(U$2-CS)") (class "Default")
      (node (ref "D2") (pin "A") (pinfunction "A_A") (pintype "passive"))
      (node (ref "RSENSE") (pin "1") (pinfunction "1_1") (pintype "passive"))
      (node (ref "U$2") (pin "P$13") (pinfunction "CS_P$13") (pintype "bidirectional"))
    )
    (net (code "70") (name "Net-(U$2-DITH)") (class "Default")
      (node (ref "CRST") (pin "2") (pinfunction "2_2") (pintype "passive"))
      (node (ref "U$2") (pin "P$15") (pinfunction "DITH_P$15") (pintype "bidirectional"))
    )
    (net (code "71") (name "Net-(U$2-EN)") (class "Default")
      (node (ref "CFT") (pin "1") (pinfunction "1_1") (pintype "passive"))
      (node (ref "RUV1") (pin "2") (pinfunction "2_2") (pintype "passive"))
      (node (ref "RUV2") (pin "1") (pinfunction "1_1") (pintype "passive"))
      (node (ref "U$2") (pin "P$2") (pinfunction "EN_P$2") (pintype "bidirectional"))
    )
    (net (code "72") (name "Net-(U$2-FB)") (class "Default")
      (node (ref "CCOMP") (pin "2") (pinfunction "2_2") (pintype "passive"))
      (node (ref "CCOMP2") (pin "2") (pinfunction "2_2") (pintype "passive"))
      (node (ref "RCOMP1") (pin "2") (pinfunction "2_2") (pintype "passive"))
      (node (ref "RFBT1") (pin "1") (pinfunction "1_1") (pintype "passive"))
      (node (ref "RFPP2") (pin "1") (pinfunction "1_1") (pintype "passive"))
      (node (ref "U$2") (pin "P$8") (pinfunction "FB_P$8") (pintype "bidirectional"))
    )
    (net (code "73") (name "Net-(U$2-RAMP)") (class "Default")
      (node (ref "CRAMP") (pin "1") (pinfunction "1_1") (pintype "passive"))
      (node (ref "RRAMP") (pin "2") (pinfunction "2_2") (pintype "passive"))
      (node (ref "U$2") (pin "P$4") (pinfunction "RAMP_P$4") (pintype "bidirectional"))
    )
    (net (code "74") (name "Net-(U$2-RT)") (class "Default")
      (node (ref "RT1") (pin "1") (pinfunction "1_1") (pintype "passive"))
      (node (ref "U$2") (pin "P$5") (pinfunction "RT_P$5") (pintype "bidirectional"))
    )
    (net (code "75") (name "Net-(U$2-SS)") (class "Default")
      (node (ref "CSS") (pin "1") (pinfunction "1_1") (pintype "passive"))
      (node (ref "U$2") (pin "P$3") (pinfunction "SS_P$3") (pintype "bidirectional"))
    )
    (net (code "76") (name "Net-(U$2-SW)") (class "Default")
      (node (ref "CBOOT") (pin "2") (pinfunction "2_2") (pintype "passive"))
      (node (ref "D2") (pin "C") (pinfunction "C_C") (pintype "passive"))
      (node (ref "Q1") (pin "1") (pinfunction "S_1") (pintype "passive"))
      (node (ref "Q1") (pin "2") (pinfunction "S_2") (pintype "passive"))
      (node (ref "Q1") (pin "3") (pinfunction "S_3") (pintype "passive"))
      (node (ref "U$2") (pin "P$12") (pinfunction "SW_P$12") (pintype "bidirectional"))
      (node (ref "U$3") (pin "P$2") (pinfunction "P$2_P$2") (pintype "bidirectional"))
    )
    (net (code "77") (name "Net-(U$2-VCC)") (class "Default")
      (node (ref "CVCC") (pin "1") (pinfunction "1_1") (pintype "passive"))
      (node (ref "RRAMP") (pin "1") (pinfunction "1_1") (pintype "passive"))
      (node (ref "U$2") (pin "P$9") (pinfunction "VCC_P$9") (pintype "bidirectional"))
    )
    (net (code "78") (name "OUT1") (class "Default")
      (node (ref "HILO") (pin "1") (pinfunction "1OUT_1") (pintype "output"))
      (node (ref "R15") (pin "1") (pinfunction "1_1") (pintype "passive"))
      (node (ref "R23") (pin "2") (pinfunction "2_2") (pintype "passive"))
      (node (ref "R24") (pin "1") (pinfunction "1_1") (pintype "passive"))
      (node (ref "R29") (pin "1") (pinfunction "1_1") (pintype "passive"))
      (node (ref "R31") (pin "1") (pinfunction "1_1") (pintype "passive"))
      (node (ref "R7") (pin "1") (pinfunction "1_1") (pintype "passive"))
    )
    (net (code "79") (name "VCC") (class "Default")
      (node (ref "BOOST") (pin "1") (pinfunction "FB_1") (pintype "input"))
      (node (ref "C2") (pin "1") (pinfunction "1_1") (pintype "passive"))
      (node (ref "C3") (pin "1") (pinfunction "1_1") (pintype "passive"))
      (node (ref "C4") (pin "1") (pinfunction "1_1") (pintype "passive"))
      (node (ref "DIGI-1-AMP") (pin "8") (pinfunction "VCC_8") (pintype "power_in"))
      (node (ref "DIGI-2-AMP") (pin "8") (pinfunction "VCC_8") (pintype "power_in"))
      (node (ref "HILO") (pin "8") (pinfunction "VCC_8") (pintype "power_in"))
      (node (ref "LOHI") (pin "8") (pinfunction "VCC_8") (pintype "power_in"))
      (node (ref "R34") (pin "1") (pinfunction "1_1") (pintype "passive"))
      (node (ref "R39") (pin "1") (pinfunction "1_1") (pintype "passive"))
      (node (ref "R4") (pin "1") (pinfunction "1_1") (pintype "passive"))
      (node (ref "R44") (pin "1") (pinfunction "1_1") (pintype "passive"))
      (node (ref "R46") (pin "1") (pinfunction "1_1") (pintype "passive"))
      (node (ref "R47") (pin "1") (pinfunction "1_1") (pintype "passive"))
    )
    (net (code "80") (name "VDD") (class "Default")
      (node (ref "CFT") (pin "2") (pinfunction "2_2") (pintype "passive"))
      (node (ref "CIO") (pin "2") (pinfunction "2_2") (pintype "passive"))
      (node (ref "COUT") (pin "-") (pinfunction "-_-") (pintype "passive"))
      (node (ref "COUTX") (pin "2") (pinfunction "2_2") (pintype "passive"))
      (node (ref "CRAMP") (pin "2") (pinfunction "2_2") (pintype "passive"))
      (node (ref "CRST") (pin "1") (pinfunction "1_1") (pintype "passive"))
      (node (ref "CSS") (pin "2") (pinfunction "2_2") (pintype "passive"))
      (node (ref "CVCC") (pin "2") (pinfunction "2_2") (pintype "passive"))
      (node (ref "HILO") (pin "3") (pinfunction "1IN+_3") (pintype "input"))
      (node (ref "HILO") (pin "4") (pinfunction "GND_4") (pintype "passive"))
      (node (ref "HILO") (pin "5") (pinfunction "2IN+_5") (pintype "input"))
      (node (ref "LOHI") (pin "4") (pinfunction "GND_4") (pintype "passive"))
      (node (ref "RFBB1") (pin "2") (pinfunction "2_2") (pintype "passive"))
      (node (ref "RSENSE") (pin "2") (pinfunction "2_2") (pintype "passive"))
      (node (ref "RT") (pin "1") (pinfunction "1_1") (pintype "passive"))
      (node (ref "RUV3") (pin "1") (pinfunction "1_1") (pintype "passive"))
      (node (ref "U$2") (pin "P$14") (pinfunction "CSG_P$14") (pintype "bidirectional"))
      (node (ref "U$2") (pin "P$6") (pinfunction "GND_P$6") (pintype "bidirectional"))
    )
  )
)
